# main.net
KiCad netlist of a schematic drawn in Altium Designer
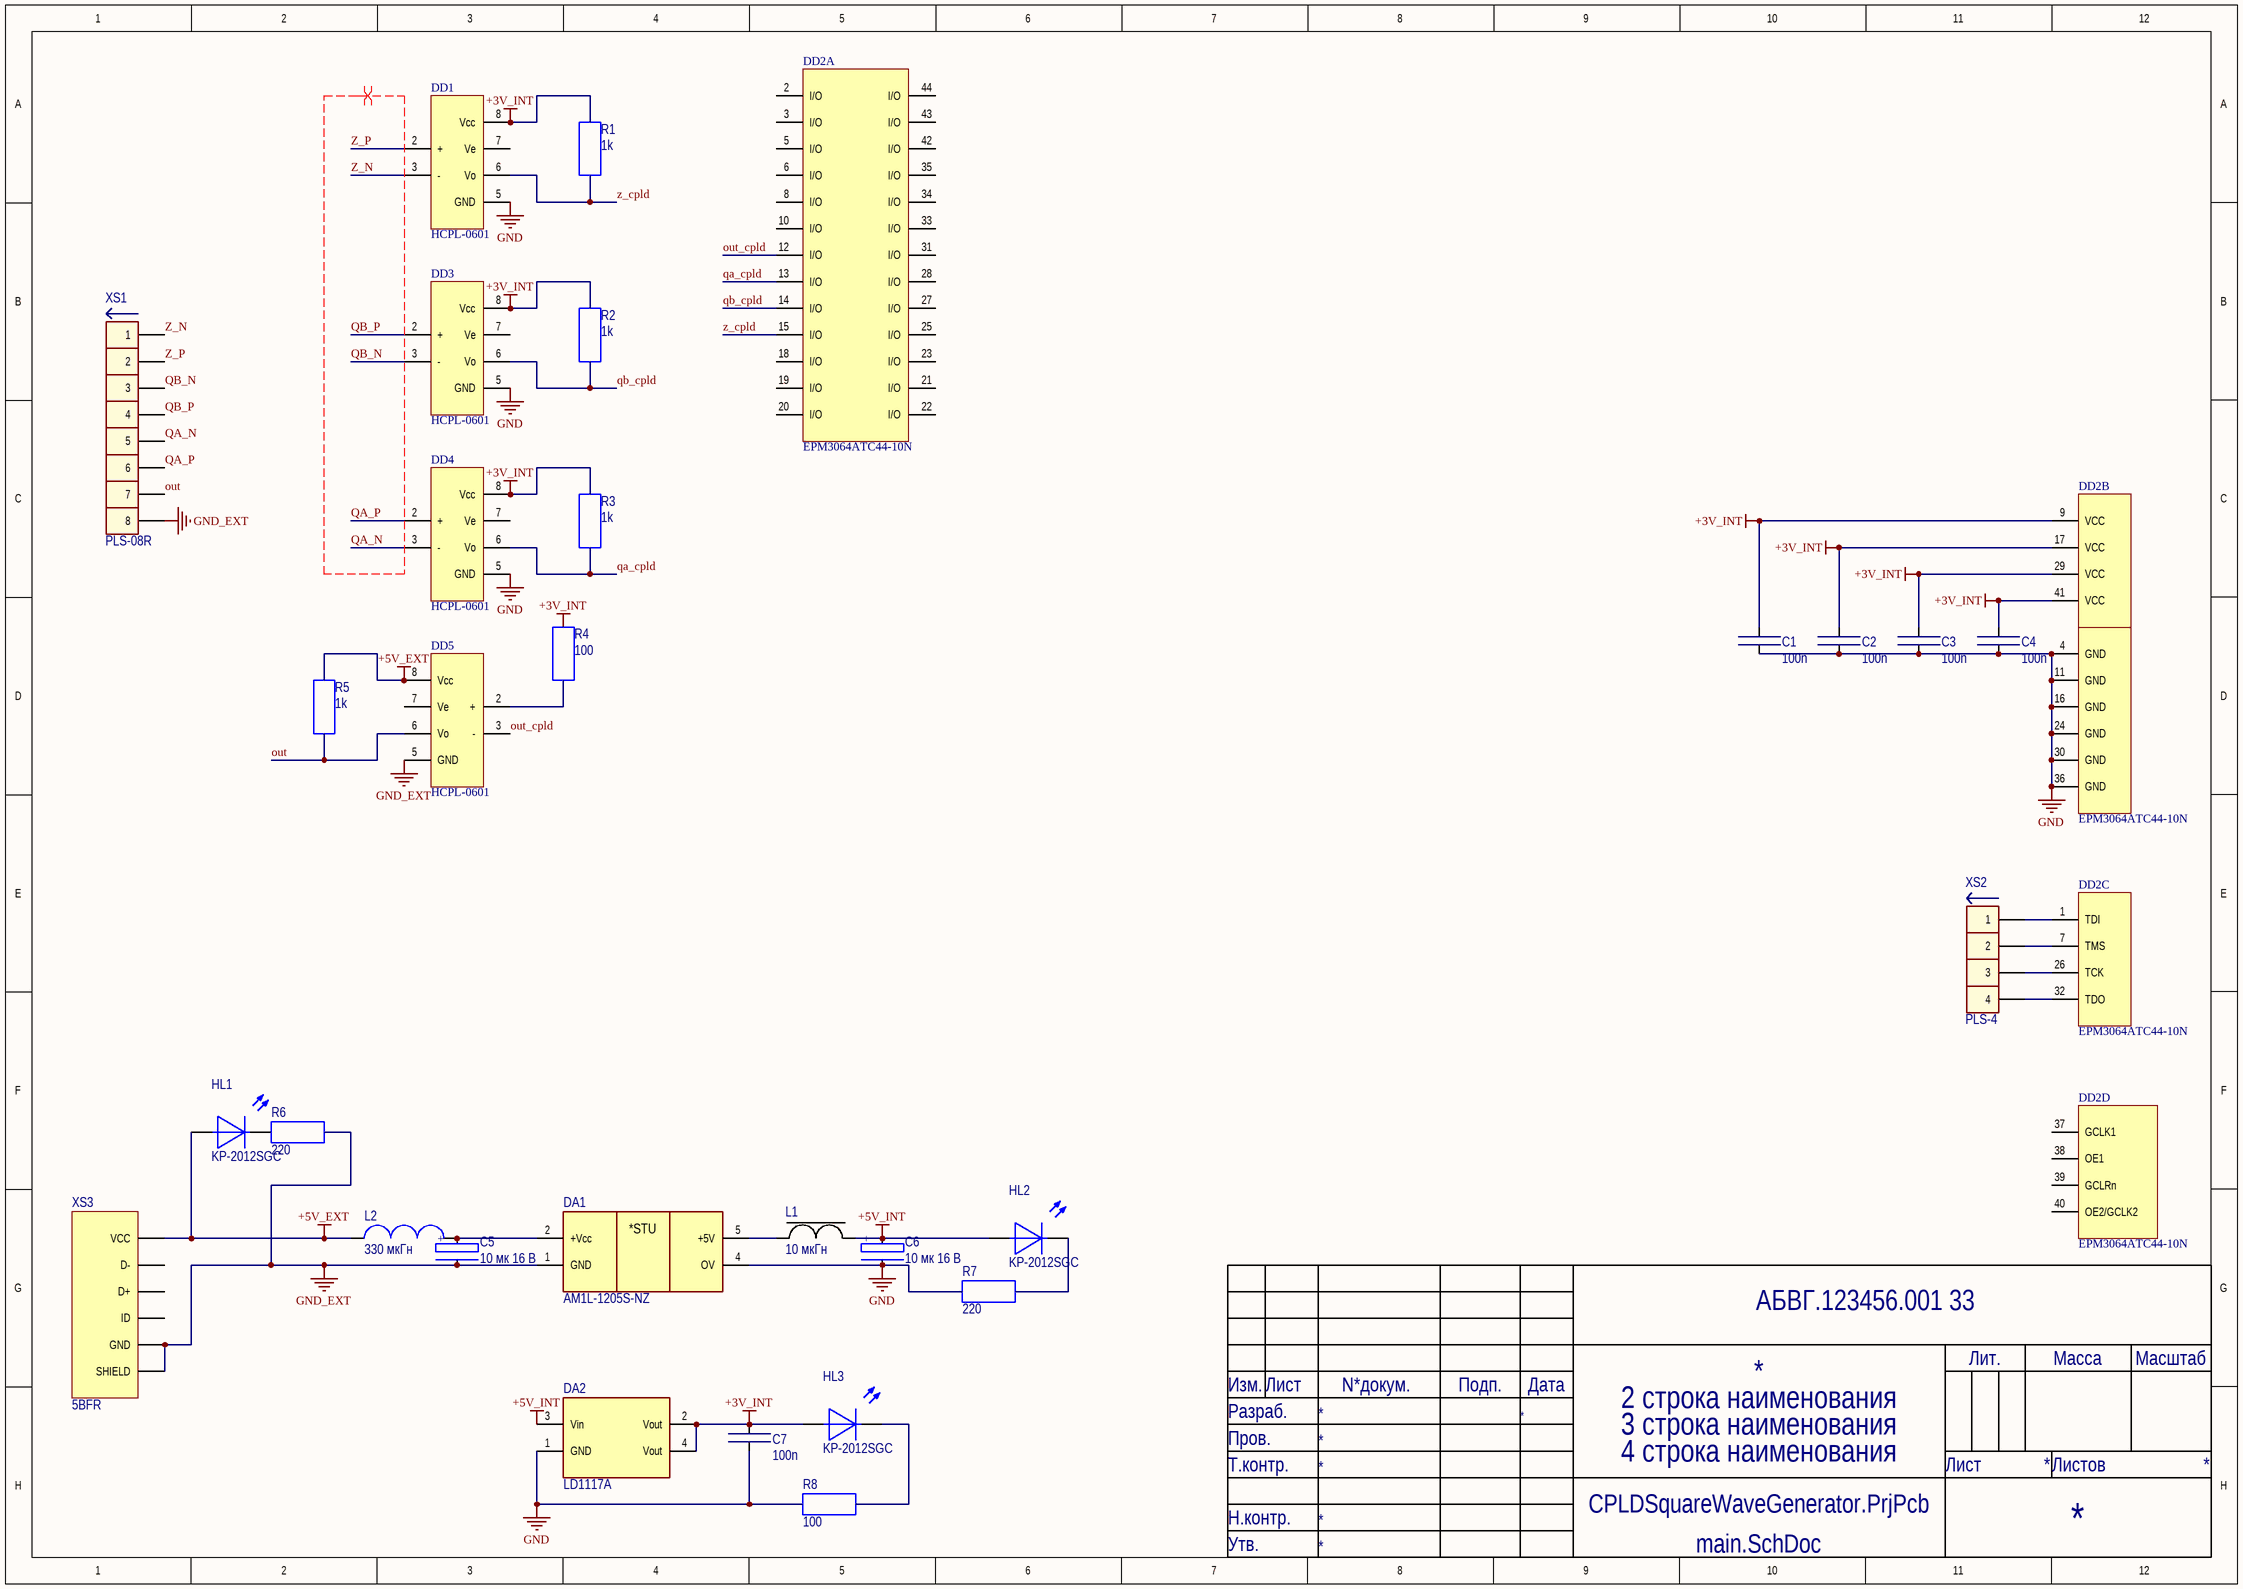
[diagram p0: main.SchDoc]

(export (version "E")
  (design (tool "Eeschema 10.0.6"))
  (components
    (comp (ref "C1")
      (value "100n")
      (footprint "SMDRC0603")
      (description "Generic capasitor non-polar")
      (fields (field (name "PARTNUMBER") "Capacitor 0603 100n"))
      (libsource (lib "library") (part "Capacitor"))
    )
    (comp (ref "C2")
      (value "100n")
      (footprint "SMDRC0603")
      (description "Generic capasitor non-polar")
      (fields (field (name "PARTNUMBER") "Capacitor 0603 100n"))
      (libsource (lib "library") (part "Capacitor"))
    )
    (comp (ref "C3")
      (value "100n")
      (footprint "SMDRC0603")
      (description "Generic capasitor non-polar")
      (fields (field (name "PARTNUMBER") "Capacitor 0603 100n"))
      (libsource (lib "library") (part "Capacitor"))
    )
    (comp (ref "C4")
      (value "100n")
      (footprint "SMDRC0603")
      (description "Generic capasitor non-polar")
      (fields (field (name "PARTNUMBER") "Capacitor 0603 100n"))
      (libsource (lib "library") (part "Capacitor"))
    )
    (comp (ref "C5")
      (value "10 мк 16 В")
      (footprint "Cap:CAP_POLAR_ELLYTE_B")
      (description "10uF 16V Polar SMD cap")
      (fields
        (field (name "MANUFACTURERPARTNUMBER") "CA016M0010REB-0405")
        (field (name "MANUFACTURER") "YAGEO")
      )
      (libsource (lib "Cap") (part "10000_016"))
    )
    (comp (ref "C6")
      (value "10 мк 16 В")
      (footprint "Cap:CAP_POLAR_ELLYTE_B")
      (description "10uF 16V Polar SMD cap")
      (fields
        (field (name "MANUFACTURERPARTNUMBER") "CA016M0010REB-0405")
        (field (name "MANUFACTURER") "YAGEO")
      )
      (libsource (lib "Cap") (part "10000_016"))
    )
    (comp (ref "C7")
      (value "100n")
      (footprint "SMDRC0603")
      (description "Generic capasitor non-polar")
      (fields (field (name "PARTNUMBER") "Capacitor 0603 100n"))
      (libsource (lib "library") (part "Capacitor"))
    )
    (comp (ref "DA1")
      (value "AM1L-1205S-NZ")
      (footprint "aimtec:SOP254P1120X625-8M")
      (description "DC/DC Isolation")
      (fields (field (name "MANUFACTURER") "AIMTEC") (field (name "MANUFACTURERPARTNUMBER") "AM1L-1205S-NZ"))
      (libsource (lib "Power") (part "AM1L-1205S-NZ"))
    )
    (comp (ref "DA2")
      (value "LD1117A")
      (footprint "Standard:SOT230P700X180-4L")
      (description "LDO регулятор напряжения 3.3V 1.0A Positive")
      (fields
        (field (name "MANUFACTURER") "STMicroelectronics")
        (field (name "MANUFACTURERPARTNUMBER") "LD1117AS33TR")
      )
      (libsource (lib "Power") (part "LD1117AS33TR"))
    )
    (comp (ref "DD1")
      (value "HCPL-0601")
      (footprint "Interface:HCPL-1601")
      (description "OPTOISO 3.75KV OPN COLLECTOR 8SO")
      (fields (field (name "MANUFACTURER") "Fairchild Semiconductor"))
      (libsource (lib "Interface") (part "HCPL-0601-500E"))
    )
    (comp (ref "DD2")
      (value "EPM3064ATC44-10N")
      (footprint "CPLD:TQFP80P1200X1230X120-44N")
      (description "MAX 3000A, 64 MACROCELLS")
      (fields (field (name "MANUFACTURER") "Altera"))
      (libsource (lib "CPLD") (part "EPM3064ATC44"))
    )
    (comp (ref "DD3")
      (value "HCPL-0601")
      (footprint "Interface:HCPL-1601")
      (description "OPTOISO 3.75KV OPN COLLECTOR 8SO")
      (fields (field (name "MANUFACTURER") "Fairchild Semiconductor"))
      (libsource (lib "Interface") (part "HCPL-0601-500E"))
    )
    (comp (ref "DD4")
      (value "HCPL-0601")
      (footprint "Interface:HCPL-1601")
      (description "OPTOISO 3.75KV OPN COLLECTOR 8SO")
      (fields (field (name "MANUFACTURER") "Fairchild Semiconductor"))
      (libsource (lib "Interface") (part "HCPL-0601-500E"))
    )
    (comp (ref "DD5")
      (value "HCPL-0601")
      (footprint "Interface:HCPL-1601")
      (description "OPTOISO 3.75KV OPN COLLECTOR 8SO")
      (fields (field (name "MANUFACTURER") "Fairchild Semiconductor"))
      (libsource (lib "") (part "HCPL-0601-500E_1"))
    )
    (comp (ref "HL1")
      (value "KP-2012SGC")
      (footprint "Indicator:DIOMELF2012M")
      (description "Diod LED SMD Green")
      (libsource (lib "Indicator") (part "LED1_G"))
    )
    (comp (ref "HL2")
      (value "KP-2012SGC")
      (footprint "Indicator:DIOMELF2012M")
      (description "Diod LED SMD Green")
      (libsource (lib "Indicator") (part "LED1_G"))
    )
    (comp (ref "HL3")
      (value "KP-2012SGC")
      (footprint "Indicator:DIOMELF2012M")
      (description "Diod LED SMD Green")
      (libsource (lib "Indicator") (part "LED1_G"))
    )
    (comp (ref "L1")
      (value "10 мкГн")
      (footprint "Inductor:MLZ2012")
      (description "Катушка 500mA 10мкГн")
      (fields (field (name "MANUFACTURERPARTNUMBER") "MPZ1608S181A") (field (name "MANUFACTURER") "TDK"))
      (libsource (lib "Inductor") (part "MLZ2012N100LT"))
    )
    (comp (ref "L2")
      (value "330 мкГн")
      (footprint "Inductor:INDP7972X50M")
      (description "Inductor")
      (fields (field (name "MANUFACTURERPARTNUMBER") "SCD0705T-331K-N"))
      (libsource (lib "Inductor") (part "SCD0705T-331K-N"))
    )
    (comp (ref "R1")
      (value "1k")
      (footprint "SMDRC0603")
      (description "Generic resistor")
      (fields (field (name "PARTNUMBER") "Resistor 0603 1k"))
      (libsource (lib "") (part "Resistor_2"))
    )
    (comp (ref "R2")
      (value "1k")
      (footprint "SMDRC0603")
      (description "Generic resistor")
      (fields (field (name "PARTNUMBER") "Resistor 0603 1k"))
      (libsource (lib "") (part "Resistor_2"))
    )
    (comp (ref "R3")
      (value "1k")
      (footprint "SMDRC0603")
      (description "Generic resistor")
      (fields (field (name "PARTNUMBER") "Resistor 0603 1k"))
      (libsource (lib "") (part "Resistor_2"))
    )
    (comp (ref "R4")
      (value "100")
      (footprint "SMDRC0603")
      (description "Generic resistor")
      (fields (field (name "PARTNUMBER") "Resistor 0603 100"))
      (libsource (lib "") (part "Resistor_2"))
    )
    (comp (ref "R5")
      (value "1k")
      (footprint "SMDRC0603")
      (description "Generic resistor")
      (fields (field (name "PARTNUMBER") "Resistor 0603 1k"))
      (libsource (lib "") (part "Resistor_2"))
    )
    (comp (ref "R6")
      (value "220")
      (footprint "SMDRC0603")
      (description "Generic resistor")
      (fields (field (name "PARTNUMBER") "Resistor 0603 220"))
      (libsource (lib "library") (part "Resistor"))
    )
    (comp (ref "R7")
      (value "220")
      (footprint "SMDRC0603")
      (description "Generic resistor")
      (fields (field (name "PARTNUMBER") "Resistor 0603 220"))
      (libsource (lib "library") (part "Resistor"))
    )
    (comp (ref "R8")
      (value "100")
      (footprint "SMDRC0603")
      (description "Generic resistor")
      (fields (field (name "PARTNUMBER") "Resistor 0603 100"))
      (libsource (lib "") (part "Resistor_1"))
    )
    (comp (ref "XS1")
      (value "partnumber")
      (footprint "Connector:PLS-08R1")
      (description "Male 8-pin connection")
      (fields (field (name "MANUFACTURERPARTNUMBER") "PLS-08R"))
      (libsource (lib "Connector") (part "Con8_M PLS-08MR"))
    )
    (comp (ref "XS2")
      (value "PLS-4")
      (footprint "Connector:PLS-04")
      (description "Male 4-pin connection")
      (libsource (lib "Connector") (part "Con4_M_PLS-4"))
    )
    (comp (ref "XS3")
      (value "5BFR")
      (footprint "Connector:USB2.0microB")
      (description "Роезтка microUSB угловая")
      (fields (field (name "MANUFACTURER") "?") (field (name "MANUFACTURERPARTNUMBER") "microUSB 5BFR"))
      (libsource (lib "Connector") (part "USB2.0-microB 5BFR"))
    )
  )
  (nets
    (net (code "1") (name "+3V_INT") (class "Default")
      (node (ref "C1") (pin "2") (pintype "passive"))
      (node (ref "C2") (pin "2") (pintype "passive"))
      (node (ref "C3") (pin "2") (pintype "passive"))
      (node (ref "C4") (pin "2") (pintype "passive"))
      (node (ref "C7") (pin "2") (pintype "passive"))
      (node (ref "DA2") (pin "2") (pinfunction "Vout_2") (pintype "passive"))
      (node (ref "DA2") (pin "4") (pinfunction "Vout_4") (pintype "passive"))
      (node (ref "DD1") (pin "8") (pinfunction "Vcc_8") (pintype "power_in"))
      (node (ref "DD2") (pin "17") (pinfunction "VCC_17") (pintype "passive"))
      (node (ref "DD2") (pin "29") (pinfunction "VCC_29") (pintype "passive"))
      (node (ref "DD2") (pin "41") (pinfunction "VCC_41") (pintype "passive"))
      (node (ref "DD2") (pin "9") (pinfunction "VCC_9") (pintype "passive"))
      (node (ref "DD3") (pin "8") (pinfunction "Vcc_8") (pintype "power_in"))
      (node (ref "DD4") (pin "8") (pinfunction "Vcc_8") (pintype "power_in"))
      (node (ref "HL3") (pin "1") (pinfunction "1_1") (pintype "passive"))
      (node (ref "R1") (pin "2") (pinfunction "2_2") (pintype "passive"))
      (node (ref "R2") (pin "2") (pinfunction "2_2") (pintype "passive"))
      (node (ref "R3") (pin "2") (pinfunction "2_2") (pintype "passive"))
      (node (ref "R4") (pin "2") (pinfunction "2_2") (pintype "passive"))
    )
    (net (code "2") (name "+5V_EXT") (class "Default")
      (node (ref "DD5") (pin "8") (pinfunction "Vcc_8") (pintype "power_in"))
      (node (ref "HL1") (pin "1") (pinfunction "1_1") (pintype "passive"))
      (node (ref "L2") (pin "2") (pinfunction "2_2") (pintype "passive"))
      (node (ref "R5") (pin "2") (pinfunction "2_2") (pintype "passive"))
      (node (ref "XS3") (pin "VCC") (pinfunction "VCC_VCC") (pintype "passive"))
    )
    (net (code "3") (name "+5V_INT") (class "Default")
      (node (ref "C6") (pin "2") (pinfunction "+_2") (pintype "passive"))
      (node (ref "DA2") (pin "3") (pinfunction "Vin_3") (pintype "passive"))
      (node (ref "HL2") (pin "1") (pinfunction "1_1") (pintype "passive"))
      (node (ref "L1") (pin "2") (pinfunction "2_2") (pintype "passive"))
    )
    (net (code "4") (name "/QA_N") (class "Default")
      (node (ref "DD4") (pin "3") (pinfunction "-_3") (pintype "passive"))
      (node (ref "XS1") (pin "5") (pinfunction "5_5") (pintype "passive"))
    )
    (net (code "5") (name "/QA_P") (class "Default")
      (node (ref "DD4") (pin "2") (pinfunction "+_2") (pintype "passive"))
      (node (ref "XS1") (pin "6") (pinfunction "6_6") (pintype "passive"))
    )
    (net (code "6") (name "/QB_N") (class "Default")
      (node (ref "DD3") (pin "3") (pinfunction "-_3") (pintype "passive"))
      (node (ref "XS1") (pin "3") (pinfunction "3_3") (pintype "passive"))
    )
    (net (code "7") (name "/QB_P") (class "Default")
      (node (ref "DD3") (pin "2") (pinfunction "+_2") (pintype "passive"))
      (node (ref "XS1") (pin "4") (pinfunction "4_4") (pintype "passive"))
    )
    (net (code "8") (name "/Z_N") (class "Default")
      (node (ref "DD1") (pin "3") (pinfunction "-_3") (pintype "passive"))
      (node (ref "XS1") (pin "1") (pinfunction "1_1") (pintype "passive"))
    )
    (net (code "9") (name "/Z_P") (class "Default")
      (node (ref "DD1") (pin "2") (pinfunction "+_2") (pintype "passive"))
      (node (ref "XS1") (pin "2") (pinfunction "2_2") (pintype "passive"))
    )
    (net (code "10") (name "/out") (class "Default")
      (node (ref "DD5") (pin "6") (pinfunction "Vo_6") (pintype "open_collector"))
      (node (ref "R5") (pin "1") (pinfunction "1_1") (pintype "passive"))
      (node (ref "XS1") (pin "7") (pinfunction "7_7") (pintype "passive"))
    )
    (net (code "11") (name "/out_cpld") (class "Default")
      (node (ref "DD2") (pin "12") (pinfunction "I/O_12") (pintype "passive"))
      (node (ref "DD5") (pin "3") (pinfunction "-_3") (pintype "passive"))
    )
    (net (code "12") (name "/qa_cpld") (class "Default")
      (node (ref "DD2") (pin "13") (pinfunction "I/O_13") (pintype "passive"))
      (node (ref "DD4") (pin "6") (pinfunction "Vo_6") (pintype "open_collector"))
      (node (ref "R3") (pin "1") (pinfunction "1_1") (pintype "passive"))
    )
    (net (code "13") (name "/qb_cpld") (class "Default")
      (node (ref "DD2") (pin "14") (pinfunction "I/O_14") (pintype "passive"))
      (node (ref "DD3") (pin "6") (pinfunction "Vo_6") (pintype "open_collector"))
      (node (ref "R2") (pin "1") (pinfunction "1_1") (pintype "passive"))
    )
    (net (code "14") (name "/z_cpld") (class "Default")
      (node (ref "DD1") (pin "6") (pinfunction "Vo_6") (pintype "open_collector"))
      (node (ref "DD2") (pin "15") (pinfunction "I/O_15") (pintype "passive"))
      (node (ref "R1") (pin "1") (pinfunction "1_1") (pintype "passive"))
    )
    (net (code "15") (name "GND") (class "Default")
      (node (ref "C1") (pin "1") (pintype "passive"))
      (node (ref "C2") (pin "1") (pintype "passive"))
      (node (ref "C3") (pin "1") (pintype "passive"))
      (node (ref "C4") (pin "1") (pintype "passive"))
      (node (ref "C6") (pin "1") (pinfunction "-_1") (pintype "passive"))
      (node (ref "C7") (pin "1") (pintype "passive"))
      (node (ref "DA1") (pin "4") (pinfunction "OV_4") (pintype "power_in"))
      (node (ref "DA2") (pin "1") (pinfunction "GND_1") (pintype "passive"))
      (node (ref "DD1") (pin "5") (pinfunction "GND_5") (pintype "power_in"))
      (node (ref "DD2") (pin "11") (pinfunction "GND_11") (pintype "passive"))
      (node (ref "DD2") (pin "16") (pinfunction "GND_16") (pintype "passive"))
      (node (ref "DD2") (pin "24") (pinfunction "GND_24") (pintype "passive"))
      (node (ref "DD2") (pin "30") (pinfunction "GND_30") (pintype "passive"))
      (node (ref "DD2") (pin "36") (pinfunction "GND_36") (pintype "passive"))
      (node (ref "DD2") (pin "4") (pinfunction "GND_4") (pintype "passive"))
      (node (ref "DD3") (pin "5") (pinfunction "GND_5") (pintype "power_in"))
      (node (ref "DD4") (pin "5") (pinfunction "GND_5") (pintype "power_in"))
      (node (ref "R7") (pin "2") (pinfunction "2_2") (pintype "passive"))
      (node (ref "R8") (pin "1") (pinfunction "1_1") (pintype "passive"))
    )
    (net (code "16") (name "GND_EXT") (class "Default")
      (node (ref "C5") (pin "1") (pinfunction "-_1") (pintype "passive"))
      (node (ref "DA1") (pin "1") (pinfunction "GND_1") (pintype "power_in"))
      (node (ref "DD5") (pin "5") (pinfunction "GND_5") (pintype "power_in"))
      (node (ref "R6") (pin "1") (pinfunction "1_1") (pintype "passive"))
      (node (ref "XS1") (pin "8") (pinfunction "8_8") (pintype "passive"))
      (node (ref "XS3") (pin "GND") (pinfunction "GND_GND") (pintype "passive"))
      (node (ref "XS3") (pin "SHIELD") (pinfunction "SHIELD_SHIELD") (pintype "passive"))
    )
    (net (code "17") (name "Net-(C5-+)") (class "Default")
      (node (ref "C5") (pin "2") (pinfunction "+_2") (pintype "passive"))
      (node (ref "DA1") (pin "2") (pinfunction "+Vcc_2") (pintype "power_in"))
      (node (ref "L2") (pin "1") (pinfunction "1_1") (pintype "passive"))
    )
    (net (code "18") (name "Net-(DA1-+5V)") (class "Default")
      (node (ref "DA1") (pin "5") (pinfunction "+5V_5") (pintype "power_in"))
      (node (ref "L1") (pin "1") (pinfunction "1_1") (pintype "passive"))
    )
    (net (code "19") (name "Net-(DD2C-TCK)") (class "Default")
      (node (ref "DD2") (pin "26") (pinfunction "TCK_26") (pintype "passive"))
      (node (ref "XS2") (pin "3") (pinfunction "3_3") (pintype "passive"))
    )
    (net (code "20") (name "Net-(DD2C-TDI)") (class "Default")
      (node (ref "DD2") (pin "1") (pinfunction "TDI_1") (pintype "passive"))
      (node (ref "XS2") (pin "1") (pinfunction "1_1") (pintype "passive"))
    )
    (net (code "21") (name "Net-(DD2C-TDO)") (class "Default")
      (node (ref "DD2") (pin "32") (pinfunction "TDO_32") (pintype "passive"))
      (node (ref "XS2") (pin "4") (pinfunction "4_4") (pintype "passive"))
    )
    (net (code "22") (name "Net-(DD2C-TMS)") (class "Default")
      (node (ref "DD2") (pin "7") (pinfunction "TMS_7") (pintype "passive"))
      (node (ref "XS2") (pin "2") (pinfunction "2_2") (pintype "passive"))
    )
    (net (code "23") (name "Net-(DD5-+)") (class "Default")
      (node (ref "DD5") (pin "2") (pinfunction "+_2") (pintype "passive"))
      (node (ref "R4") (pin "1") (pinfunction "1_1") (pintype "passive"))
    )
    (net (code "24") (name "Net-(HL1-Pad2)") (class "Default")
      (node (ref "HL1") (pin "2") (pinfunction "2_2") (pintype "passive"))
      (node (ref "R6") (pin "2") (pinfunction "2_2") (pintype "passive"))
    )
    (net (code "25") (name "Net-(HL2-Pad2)") (class "Default")
      (node (ref "HL2") (pin "2") (pinfunction "2_2") (pintype "passive"))
      (node (ref "R7") (pin "1") (pinfunction "1_1") (pintype "passive"))
    )
    (net (code "26") (name "Net-(HL3-Pad2)") (class "Default")
      (node (ref "HL3") (pin "2") (pinfunction "2_2") (pintype "passive"))
      (node (ref "R8") (pin "2") (pinfunction "2_2") (pintype "passive"))
    )
    (net (code "27") (name "unconnected-(DD1-Ve-Pad7)") (class "Default")
      (node (ref "DD1") (pin "7") (pinfunction "Ve_7") (pintype "passive"))
    )
    (net (code "28") (name "unconnected-(DD2A-I{slash}O-Pad2)") (class "Default")
      (node (ref "DD2") (pin "2") (pinfunction "I/O_2") (pintype "passive"))
    )
    (net (code "29") (name "unconnected-(DD2A-I{slash}O-Pad3)") (class "Default")
      (node (ref "DD2") (pin "3") (pinfunction "I/O_3") (pintype "passive"))
    )
    (net (code "30") (name "unconnected-(DD2A-I{slash}O-Pad5)") (class "Default")
      (node (ref "DD2") (pin "5") (pinfunction "I/O_5") (pintype "passive"))
    )
    (net (code "31") (name "unconnected-(DD2A-I{slash}O-Pad6)") (class "Default")
      (node (ref "DD2") (pin "6") (pinfunction "I/O_6") (pintype "passive"))
    )
    (net (code "32") (name "unconnected-(DD2A-I{slash}O-Pad8)") (class "Default")
      (node (ref "DD2") (pin "8") (pinfunction "I/O_8") (pintype "passive"))
    )
    (net (code "33") (name "unconnected-(DD2A-I{slash}O-Pad10)") (class "Default")
      (node (ref "DD2") (pin "10") (pinfunction "I/O_10") (pintype "passive"))
    )
    (net (code "34") (name "unconnected-(DD2A-I{slash}O-Pad18)") (class "Default")
      (node (ref "DD2") (pin "18") (pinfunction "I/O_18") (pintype "passive"))
    )
    (net (code "35") (name "unconnected-(DD2A-I{slash}O-Pad19)") (class "Default")
      (node (ref "DD2") (pin "19") (pinfunction "I/O_19") (pintype "passive"))
    )
    (net (code "36") (name "unconnected-(DD2A-I{slash}O-Pad20)") (class "Default")
      (node (ref "DD2") (pin "20") (pinfunction "I/O_20") (pintype "passive"))
    )
    (net (code "37") (name "unconnected-(DD2A-I{slash}O-Pad21)") (class "Default")
      (node (ref "DD2") (pin "21") (pinfunction "I/O_21") (pintype "passive"))
    )
    (net (code "38") (name "unconnected-(DD2A-I{slash}O-Pad22)") (class "Default")
      (node (ref "DD2") (pin "22") (pinfunction "I/O_22") (pintype "passive"))
    )
    (net (code "39") (name "unconnected-(DD2A-I{slash}O-Pad23)") (class "Default")
      (node (ref "DD2") (pin "23") (pinfunction "I/O_23") (pintype "passive"))
    )
    (net (code "40") (name "unconnected-(DD2A-I{slash}O-Pad25)") (class "Default")
      (node (ref "DD2") (pin "25") (pinfunction "I/O_25") (pintype "passive"))
    )
    (net (code "41") (name "unconnected-(DD2A-I{slash}O-Pad27)") (class "Default")
      (node (ref "DD2") (pin "27") (pinfunction "I/O_27") (pintype "passive"))
    )
    (net (code "42") (name "unconnected-(DD2A-I{slash}O-Pad28)") (class "Default")
      (node (ref "DD2") (pin "28") (pinfunction "I/O_28") (pintype "passive"))
    )
    (net (code "43") (name "unconnected-(DD2A-I{slash}O-Pad31)") (class "Default")
      (node (ref "DD2") (pin "31") (pinfunction "I/O_31") (pintype "passive"))
    )
    (net (code "44") (name "unconnected-(DD2A-I{slash}O-Pad33)") (class "Default")
      (node (ref "DD2") (pin "33") (pinfunction "I/O_33") (pintype "passive"))
    )
    (net (code "45") (name "unconnected-(DD2A-I{slash}O-Pad34)") (class "Default")
      (node (ref "DD2") (pin "34") (pinfunction "I/O_34") (pintype "passive"))
    )
    (net (code "46") (name "unconnected-(DD2A-I{slash}O-Pad35)") (class "Default")
      (node (ref "DD2") (pin "35") (pinfunction "I/O_35") (pintype "passive"))
    )
    (net (code "47") (name "unconnected-(DD2A-I{slash}O-Pad42)") (class "Default")
      (node (ref "DD2") (pin "42") (pinfunction "I/O_42") (pintype "passive"))
    )
    (net (code "48") (name "unconnected-(DD2A-I{slash}O-Pad43)") (class "Default")
      (node (ref "DD2") (pin "43") (pinfunction "I/O_43") (pintype "passive"))
    )
    (net (code "49") (name "unconnected-(DD2A-I{slash}O-Pad44)") (class "Default")
      (node (ref "DD2") (pin "44") (pinfunction "I/O_44") (pintype "passive"))
    )
    (net (code "50") (name "unconnected-(DD2D-GCLK1-Pad37)") (class "Default")
      (node (ref "DD2") (pin "37") (pinfunction "GCLK1_37") (pintype "passive"))
    )
    (net (code "51") (name "unconnected-(DD2D-GCLRn-Pad39)") (class "Default")
      (node (ref "DD2") (pin "39") (pinfunction "GCLRn_39") (pintype "passive"))
    )
    (net (code "52") (name "unconnected-(DD2D-OE1-Pad38)") (class "Default")
      (node (ref "DD2") (pin "38") (pinfunction "OE1_38") (pintype "passive"))
    )
    (net (code "53") (name "unconnected-(DD2D-OE2{slash}GCLK2-Pad40)") (class "Default")
      (node (ref "DD2") (pin "40") (pinfunction "OE2/GCLK2_40") (pintype "passive"))
    )
    (net (code "54") (name "unconnected-(DD3-Ve-Pad7)") (class "Default")
      (node (ref "DD3") (pin "7") (pinfunction "Ve_7") (pintype "passive"))
    )
    (net (code "55") (name "unconnected-(DD4-Ve-Pad7)") (class "Default")
      (node (ref "DD4") (pin "7") (pinfunction "Ve_7") (pintype "passive"))
    )
    (net (code "56") (name "unconnected-(DD5-Ve-Pad7)") (class "Default")
      (node (ref "DD5") (pin "7") (pinfunction "Ve_7") (pintype "passive"))
    )
    (net (code "57") (name "unconnected-(XS3-PadD+)") (class "Default")
      (node (ref "XS3") (pin "D+") (pinfunction "D+_D+") (pintype "passive"))
    )
    (net (code "58") (name "unconnected-(XS3-PadD-)") (class "Default")
      (node (ref "XS3") (pin "D-") (pinfunction "D-_D-") (pintype "passive"))
    )
    (net (code "59") (name "unconnected-(XS3-PadID)") (class "Default")
      (node (ref "XS3") (pin "ID") (pinfunction "ID_ID") (pintype "passive"))
    )
  )
)
